# Digital_IO_LS.net
KiCad netlist of a schematic drawn in Altium Designer
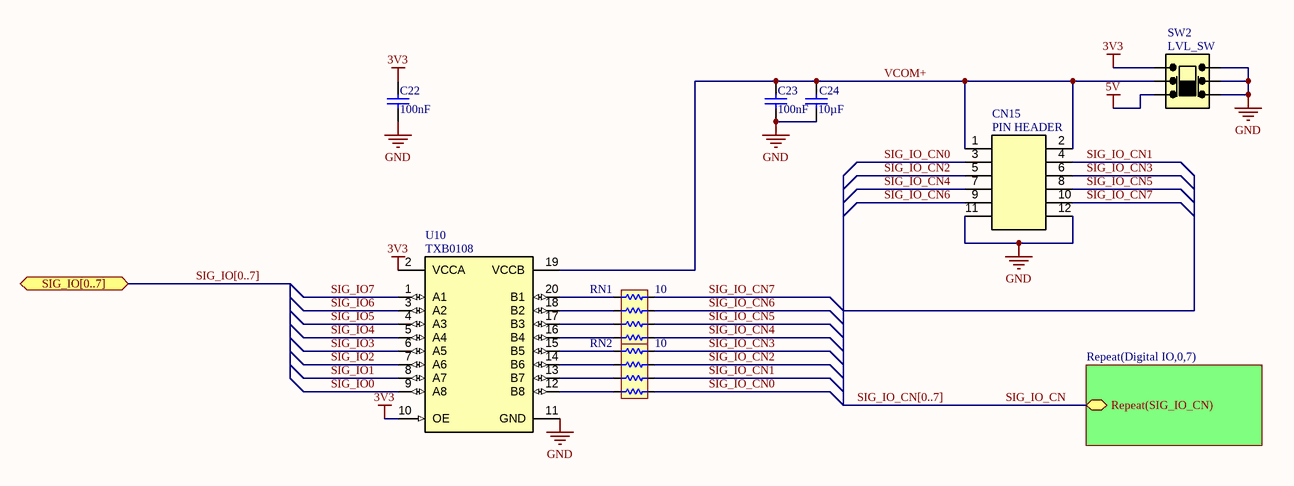
[diagram p0: Digital IO LS.SchDoc]

(export (version "E")
  (design (tool "Eeschema 10.0.6"))
  (components
    (comp (ref "C22")
      (value "100nF")
      (footprint "CAP_CHIP_0603")
      (description "0603 Multilayer Ceramic Capacitors MLCC")
      (fields (field (name "TOLERANCE") "10%") (field (name "PARTNUMBER") "CC0603KRX7R9BB104"))
      (libsource (lib "Sainsbury Wellcome Centre") (part "Cap"))
    )
    (comp (ref "C23")
      (value "100nF")
      (footprint "CAP_CHIP_0603")
      (description "0603 Multilayer Ceramic Capacitors MLCC")
      (fields (field (name "TOLERANCE") "10%") (field (name "PARTNUMBER") "CC0603KRX7R9BB104"))
      (libsource (lib "Sainsbury Wellcome Centre") (part "Cap"))
    )
    (comp (ref "C24")
      (value "10µF")
      (footprint "CAP_CHIP_0603")
      (fields
        (field (name "PARTNUMBER") "GRM188R6YA106MA73D")
        (field (name "TOLERANCE") "20%")
        (field (name "Comment") "C0603-10uF-35V")
      )
      (libsource (lib "Sainsbury Wellcome Centre") (part "Cap"))
    )
    (comp (ref "CN15")
      (value "PIN HEADER")
      (footprint "PIN_2.54_2X6P")
      (fields (field (name "PARTNUMBER") "PZ254V-12-12P"))
      (libsource (lib "Sainsbury Wellcome Centre") (part "Header_2X6P"))
    )
    (comp (ref "RN1")
      (value "10")
      (footprint "RES_ARRAY_0603")
      (fields
        (field (name "TOLERANCE") "5%")
        (field (name "PARTNUMBER") "4D03WGJ0100T5E")
        (field (name "Comment") "RN0603-10R")
      )
      (libsource (lib "Sainsbury Wellcome Centre") (part "Res Array 4P"))
    )
    (comp (ref "RN2")
      (value "10")
      (footprint "RES_ARRAY_0603")
      (fields
        (field (name "TOLERANCE") "5%")
        (field (name "PARTNUMBER") "4D03WGJ0100T5E")
        (field (name "Comment") "RN0603-10R")
      )
      (libsource (lib "Sainsbury Wellcome Centre") (part "Res Array 4P"))
    )
    (comp (ref "SW2")
      (value "LVL_SW")
      (footprint "SW_SLIDE_OS202013MT8")
      (description "Switch Slide ON ON DPDT Top Slide 0.3A 30VDC 10000Cycles PC Pins Thru-Hole Bulk")
      (fields (field (name "PARTNUMBER") "OS202013MT8QN1"))
      (libsource (lib "Sainsbury Wellcome Centre") (part "SLIDE_DPDT"))
    )
    (comp (ref "U10")
      (value "TXB0108")
      (footprint "TSSOP20_6.5X4.4_0.65E")
      (fields (field (name "PARTNUMBER") "TXB0108PWR"))
      (libsource (lib "Sainsbury Wellcome Centre") (part "TXB0108"))
    )
  )
  (nets
    (net (code "1") (name "/SIG_IO0") (class "Default")
      (node (ref "U10") (pin "9") (pinfunction "A8_9") (pintype "bidirectional"))
    )
    (net (code "2") (name "/SIG_IO1") (class "Default")
      (node (ref "U10") (pin "8") (pinfunction "A7_8") (pintype "bidirectional"))
    )
    (net (code "3") (name "/SIG_IO2") (class "Default")
      (node (ref "U10") (pin "7") (pinfunction "A6_7") (pintype "bidirectional"))
    )
    (net (code "4") (name "/SIG_IO3") (class "Default")
      (node (ref "U10") (pin "6") (pinfunction "A5_6") (pintype "bidirectional"))
    )
    (net (code "5") (name "/SIG_IO4") (class "Default")
      (node (ref "U10") (pin "5") (pinfunction "A4_5") (pintype "bidirectional"))
    )
    (net (code "6") (name "/SIG_IO5") (class "Default")
      (node (ref "U10") (pin "4") (pinfunction "A3_4") (pintype "bidirectional"))
    )
    (net (code "7") (name "/SIG_IO6") (class "Default")
      (node (ref "U10") (pin "3") (pinfunction "A2_3") (pintype "bidirectional"))
    )
    (net (code "8") (name "/SIG_IO7") (class "Default")
      (node (ref "U10") (pin "1") (pinfunction "A1_1") (pintype "bidirectional"))
    )
    (net (code "11") (name "/SIG_IO_CN0") (class "Default")
      (node (ref "CN15") (pin "3") (pinfunction "3_3") (pintype "passive"))
      (node (ref "RN2") (pin "5") (pinfunction "5_5") (pintype "passive"))
    )
    (net (code "12") (name "/SIG_IO_CN1") (class "Default")
      (node (ref "CN15") (pin "4") (pinfunction "4_4") (pintype "passive"))
      (node (ref "RN2") (pin "6") (pinfunction "6_6") (pintype "passive"))
    )
    (net (code "13") (name "/SIG_IO_CN2") (class "Default")
      (node (ref "CN15") (pin "5") (pinfunction "5_5") (pintype "passive"))
      (node (ref "RN2") (pin "7") (pinfunction "7_7") (pintype "passive"))
    )
    (net (code "14") (name "/SIG_IO_CN3") (class "Default")
      (node (ref "CN15") (pin "6") (pinfunction "6_6") (pintype "passive"))
      (node (ref "RN2") (pin "8") (pinfunction "8_8") (pintype "passive"))
    )
    (net (code "15") (name "/SIG_IO_CN4") (class "Default")
      (node (ref "CN15") (pin "7") (pinfunction "7_7") (pintype "passive"))
      (node (ref "RN1") (pin "5") (pinfunction "5_5") (pintype "passive"))
    )
    (net (code "16") (name "/SIG_IO_CN5") (class "Default")
      (node (ref "CN15") (pin "8") (pinfunction "8_8") (pintype "passive"))
      (node (ref "RN1") (pin "6") (pinfunction "6_6") (pintype "passive"))
    )
    (net (code "17") (name "/SIG_IO_CN6") (class "Default")
      (node (ref "CN15") (pin "9") (pinfunction "9_9") (pintype "passive"))
      (node (ref "RN1") (pin "7") (pinfunction "7_7") (pintype "passive"))
    )
    (net (code "18") (name "/SIG_IO_CN7") (class "Default")
      (node (ref "CN15") (pin "10") (pinfunction "10_10") (pintype "passive"))
      (node (ref "RN1") (pin "8") (pinfunction "8_8") (pintype "passive"))
    )
    (net (code "20") (name "/VCOM+") (class "Default")
      (node (ref "C23") (pin "2") (pinfunction "2_2") (pintype "passive"))
      (node (ref "C24") (pin "2") (pinfunction "2_2") (pintype "passive"))
      (node (ref "CN15") (pin "1") (pinfunction "1_1") (pintype "passive"))
      (node (ref "CN15") (pin "2") (pinfunction "2_2") (pintype "passive"))
      (node (ref "SW2") (pin "2") (pinfunction "COMA_2") (pintype "passive"))
      (node (ref "U10") (pin "19") (pinfunction "VCCB_19") (pintype "power_in"))
    )
    (net (code "21") (name "3V3") (class "Default")
      (node (ref "C22") (pin "2") (pinfunction "2_2") (pintype "passive"))
      (node (ref "SW2") (pin "3") (pinfunction "NOA_3") (pintype "passive"))
      (node (ref "U10") (pin "10") (pinfunction "OE_10") (pintype "input"))
      (node (ref "U10") (pin "2") (pinfunction "VCCA_2") (pintype "power_in"))
    )
    (net (code "22") (name "5V") (class "Default")
      (node (ref "SW2") (pin "1") (pinfunction "NCA_1") (pintype "passive"))
    )
    (net (code "23") (name "GND") (class "Default")
      (node (ref "C22") (pin "1") (pinfunction "1_1") (pintype "passive"))
      (node (ref "C23") (pin "1") (pinfunction "1_1") (pintype "passive"))
      (node (ref "C24") (pin "1") (pinfunction "1_1") (pintype "passive"))
      (node (ref "CN15") (pin "11") (pinfunction "11_11") (pintype "passive"))
      (node (ref "CN15") (pin "12") (pinfunction "12_12") (pintype "passive"))
      (node (ref "SW2") (pin "4") (pinfunction "NCB_4") (pintype "passive"))
      (node (ref "SW2") (pin "5") (pinfunction "COMB_5") (pintype "passive"))
      (node (ref "SW2") (pin "6") (pinfunction "NOB_6") (pintype "passive"))
      (node (ref "U10") (pin "11") (pinfunction "GND_11") (pintype "power_in"))
    )
    (net (code "24") (name "Net-(U10-B1)") (class "Default")
      (node (ref "RN1") (pin "1") (pinfunction "1_1") (pintype "passive"))
      (node (ref "U10") (pin "20") (pinfunction "B1_20") (pintype "bidirectional"))
    )
    (net (code "25") (name "Net-(U10-B2)") (class "Default")
      (node (ref "RN1") (pin "2") (pinfunction "2_2") (pintype "passive"))
      (node (ref "U10") (pin "18") (pinfunction "B2_18") (pintype "bidirectional"))
    )
    (net (code "26") (name "Net-(U10-B3)") (class "Default")
      (node (ref "RN1") (pin "3") (pinfunction "3_3") (pintype "passive"))
      (node (ref "U10") (pin "17") (pinfunction "B3_17") (pintype "bidirectional"))
    )
    (net (code "27") (name "Net-(U10-B4)") (class "Default")
      (node (ref "RN1") (pin "4") (pinfunction "4_4") (pintype "passive"))
      (node (ref "U10") (pin "16") (pinfunction "B4_16") (pintype "bidirectional"))
    )
    (net (code "28") (name "Net-(U10-B5)") (class "Default")
      (node (ref "RN2") (pin "1") (pinfunction "1_1") (pintype "passive"))
      (node (ref "U10") (pin "15") (pinfunction "B5_15") (pintype "bidirectional"))
    )
    (net (code "29") (name "Net-(U10-B6)") (class "Default")
      (node (ref "RN2") (pin "2") (pinfunction "2_2") (pintype "passive"))
      (node (ref "U10") (pin "14") (pinfunction "B6_14") (pintype "bidirectional"))
    )
    (net (code "30") (name "Net-(U10-B7)") (class "Default")
      (node (ref "RN2") (pin "3") (pinfunction "3_3") (pintype "passive"))
      (node (ref "U10") (pin "13") (pinfunction "B7_13") (pintype "bidirectional"))
    )
    (net (code "31") (name "Net-(U10-B8)") (class "Default")
      (node (ref "RN2") (pin "4") (pinfunction "4_4") (pintype "passive"))
      (node (ref "U10") (pin "12") (pinfunction "B8_12") (pintype "bidirectional"))
    )
  )
)
